# Termocouplers.net
KiCad netlist of a schematic drawn in Altium Designer
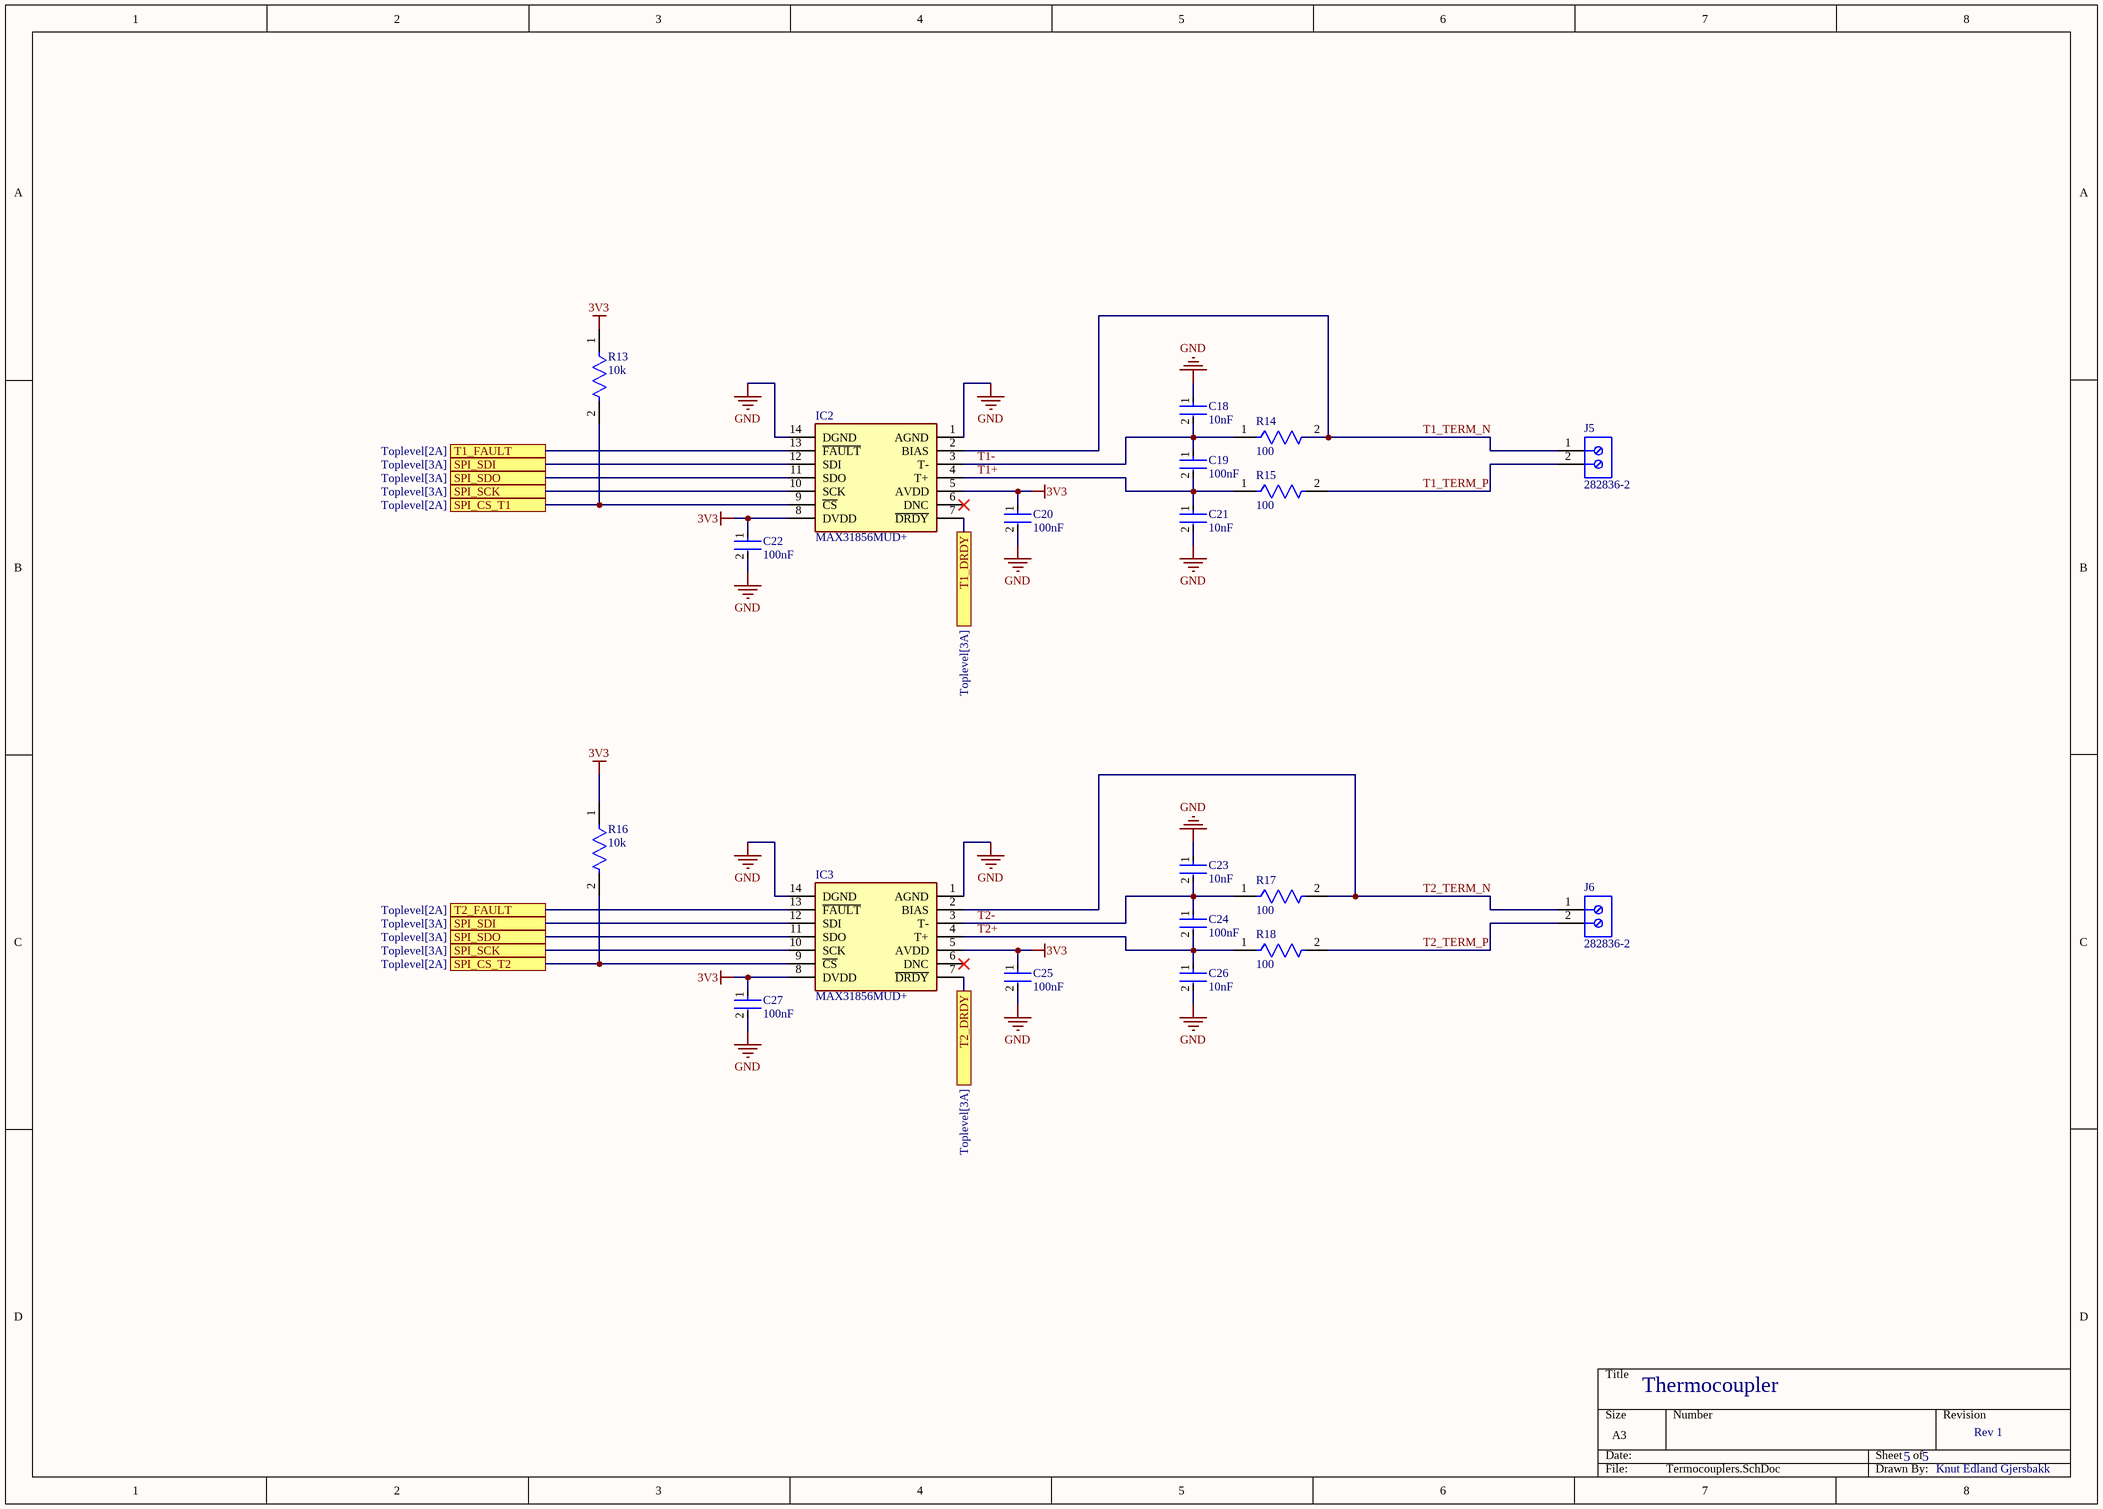
[diagram p0: Termocouplers.SchDoc]

(export (version "E")
  (design (tool "Eeschema 10.0.6"))
  (components
    (comp (ref "C18")
      (value "10nF")
      (footprint "FP-GCM188-0_1-MFG")
      (description "Ceramic Capacitor for Automotive 10nF  ±10% 100VDC X7R 0603 Paper T/R")
      (fields (field (name "VOLTAGE") "100V") (field (name "TOLERANCE") "10%"))
      (libsource (lib "Altium Content Vault") (part "02cd4be3c70576c341d710602a673aa"))
    )
    (comp (ref "C19")
      (value "100nF")
      (footprint "FP-GCM188-0_1-IPC_B")
      (description "Ceramic Capacitor for Automotive 100nF  ±10% 50VDC X8L 0603 Paper T/R")
      (fields (field (name "TOLERANCE") "10%") (field (name "VOLTAGE") "50V"))
      (libsource (lib "Altium Content Vault") (part "02cd4be3c70576c341d710602a673aa"))
    )
    (comp (ref "C20")
      (value "100nF")
      (footprint "FP-GCM188-0_1-IPC_B")
      (description "Ceramic Capacitor for Automotive 100nF  ±10% 50VDC X8L 0603 Paper T/R")
      (fields (field (name "TOLERANCE") "10%") (field (name "VOLTAGE") "50V"))
      (libsource (lib "Altium Content Vault") (part "02cd4be3c70576c341d710602a673aa"))
    )
    (comp (ref "C21")
      (value "10nF")
      (footprint "FP-GCM188-0_1-MFG")
      (description "Ceramic Capacitor for Automotive 10nF  ±10% 100VDC X7R 0603 Paper T/R")
      (fields (field (name "VOLTAGE") "100V") (field (name "TOLERANCE") "10%"))
      (libsource (lib "Altium Content Vault") (part "02cd4be3c70576c341d710602a673aa"))
    )
    (comp (ref "C22")
      (value "100nF")
      (footprint "FP-GCM188-0_1-IPC_B")
      (description "Ceramic Capacitor for Automotive 100nF  ±10% 50VDC X8L 0603 Paper T/R")
      (fields (field (name "TOLERANCE") "10%") (field (name "VOLTAGE") "50V"))
      (libsource (lib "Altium Content Vault") (part "02cd4be3c70576c341d710602a673aa"))
    )
    (comp (ref "C23")
      (value "10nF")
      (footprint "FP-GCM188-0_1-MFG")
      (description "Ceramic Capacitor for Automotive 10nF  ±10% 100VDC X7R 0603 Paper T/R")
      (fields (field (name "VOLTAGE") "100V") (field (name "TOLERANCE") "10%"))
      (libsource (lib "Altium Content Vault") (part "02cd4be3c70576c341d710602a673aa"))
    )
    (comp (ref "C24")
      (value "100nF")
      (footprint "FP-GCM188-0_1-IPC_B")
      (description "Ceramic Capacitor for Automotive 100nF  ±10% 50VDC X8L 0603 Paper T/R")
      (fields (field (name "TOLERANCE") "10%") (field (name "VOLTAGE") "50V"))
      (libsource (lib "Altium Content Vault") (part "02cd4be3c70576c341d710602a673aa"))
    )
    (comp (ref "C25")
      (value "100nF")
      (footprint "FP-GCM188-0_1-IPC_B")
      (description "Ceramic Capacitor for Automotive 100nF  ±10% 50VDC X8L 0603 Paper T/R")
      (fields (field (name "TOLERANCE") "10%") (field (name "VOLTAGE") "50V"))
      (libsource (lib "Altium Content Vault") (part "02cd4be3c70576c341d710602a673aa"))
    )
    (comp (ref "C26")
      (value "10nF")
      (footprint "FP-GCM188-0_1-MFG")
      (description "Ceramic Capacitor for Automotive 10nF  ±10% 100VDC X7R 0603 Paper T/R")
      (fields (field (name "VOLTAGE") "100V") (field (name "TOLERANCE") "10%"))
      (libsource (lib "Altium Content Vault") (part "02cd4be3c70576c341d710602a673aa"))
    )
    (comp (ref "C27")
      (value "100nF")
      (footprint "FP-GCM188-0_1-IPC_B")
      (description "Ceramic Capacitor for Automotive 100nF  ±10% 50VDC X8L 0603 Paper T/R")
      (fields (field (name "TOLERANCE") "10%") (field (name "VOLTAGE") "50V"))
      (libsource (lib "Altium Content Vault") (part "02cd4be3c70576c341d710602a673aa"))
    )
    (comp (ref "IC2")
      (value "MAX31856MUD+")
      (footprint "SamacSys:SOP65P640X110-14N")
      (description "Integrated Circuit")
      (fields (field (name "MOUSER PART NUMBER") "700-MAX31856MUD+"))
      (libsource (lib "*") (part "MAX31856MUD+"))
    )
    (comp (ref "IC3")
      (value "MAX31856MUD+")
      (footprint "SamacSys:SOP65P640X110-14N")
      (description "Integrated Circuit")
      (fields (field (name "MOUSER PART NUMBER") "700-MAX31856MUD+"))
      (libsource (lib "*") (part "MAX31856MUD+"))
    )
    (comp (ref "J5")
      (value "282836-2")
      (footprint "TECO-282836-2_V")
      (description "Female Header, Pitch 5 mm, 1 x 2 Position, Height 10 mm, Tail Length 3.5 mm, Rohs, Bulk")
      (fields (field (name "VOLTAGE") "300V") (field (name "MANUFACTURER") "TE Connectivity"))
      (libsource (lib "Altium Content Vault") (part "CN-1P-F-TB2"))
    )
    (comp (ref "J6")
      (value "282836-2")
      (footprint "TECO-282836-2_V")
      (description "Female Header, Pitch 5 mm, 1 x 2 Position, Height 10 mm, Tail Length 3.5 mm, Rohs, Bulk")
      (fields (field (name "VOLTAGE") "300V") (field (name "MANUFACTURER") "TE Connectivity"))
      (libsource (lib "Altium Content Vault") (part "CN-1P-F-TB2"))
    )
    (comp (ref "R13")
      (value "10k")
      (footprint "FP-RT0603-IPC_C")
      (description "RES SMD 10K OHM 1% 1/10W 0603\r\nRT0603FRE0710KL")
      (fields
        (field (name "MANUFACTURER") "Yageo")
        (field (name "OCTOPART") "https://octopart.com/rt0603fre0710kl-yageo-40009243")
      )
      (libsource (lib "Altium Content Vault") (part "1029c3af85768c4190bb7ad29bc67b5"))
    )
    (comp (ref "R14")
      (value "100")
      (footprint "FP-CR0603-IPC_A")
      (description "AEC-Q200 Compliant Chip Resistors 0603 100Ω 0.1W 1% 100ppm/°C")
      (libsource (lib "Altium Content Vault") (part "1029c3af85768c4190bb7ad29bc67b5"))
    )
    (comp (ref "R15")
      (value "100")
      (footprint "FP-CR0603-IPC_A")
      (description "AEC-Q200 Compliant Chip Resistors 0603 100Ω 0.1W 1% 100ppm/°C")
      (libsource (lib "Altium Content Vault") (part "1029c3af85768c4190bb7ad29bc67b5"))
    )
    (comp (ref "R16")
      (value "10k")
      (footprint "FP-RT0603-IPC_C")
      (description "RES SMD 10K OHM 1% 1/10W 0603\r\nRT0603FRE0710KL")
      (fields
        (field (name "MANUFACTURER") "Yageo")
        (field (name "OCTOPART") "https://octopart.com/rt0603fre0710kl-yageo-40009243")
      )
      (libsource (lib "Altium Content Vault") (part "1029c3af85768c4190bb7ad29bc67b5"))
    )
    (comp (ref "R17")
      (value "100")
      (footprint "FP-CR0603-IPC_A")
      (description "AEC-Q200 Compliant Chip Resistors 0603 100Ω 0.1W 1% 100ppm/°C")
      (libsource (lib "Altium Content Vault") (part "1029c3af85768c4190bb7ad29bc67b5"))
    )
    (comp (ref "R18")
      (value "100")
      (footprint "FP-CR0603-IPC_A")
      (description "AEC-Q200 Compliant Chip Resistors 0603 100Ω 0.1W 1% 100ppm/°C")
      (libsource (lib "Altium Content Vault") (part "1029c3af85768c4190bb7ad29bc67b5"))
    )
  )
  (nets
    (net (code "1") (name "/SPI_CS_T1") (class "Default")
      (node (ref "IC2") (pin "9") (pinfunction "~{CS}_9") (pintype "passive"))
      (node (ref "R13") (pin "2") (pinfunction "2_2") (pintype "passive"))
    )
    (net (code "2") (name "/SPI_CS_T2") (class "Default")
      (node (ref "IC3") (pin "9") (pinfunction "~{CS}_9") (pintype "passive"))
      (node (ref "R16") (pin "2") (pinfunction "2_2") (pintype "passive"))
    )
    (net (code "3") (name "/SPI_SCK") (class "Default")
      (node (ref "IC2") (pin "10") (pinfunction "SCK_10") (pintype "passive"))
      (node (ref "IC3") (pin "10") (pinfunction "SCK_10") (pintype "passive"))
    )
    (net (code "4") (name "/SPI_SDI") (class "Default")
      (node (ref "IC2") (pin "12") (pinfunction "SDI_12") (pintype "passive"))
      (node (ref "IC3") (pin "12") (pinfunction "SDI_12") (pintype "passive"))
    )
    (net (code "5") (name "/SPI_SDO") (class "Default")
      (node (ref "IC2") (pin "11") (pinfunction "SDO_11") (pintype "passive"))
      (node (ref "IC3") (pin "11") (pinfunction "SDO_11") (pintype "passive"))
    )
    (net (code "6") (name "/T1+") (class "Default")
      (node (ref "C19") (pin "2") (pinfunction "2_2") (pintype "passive"))
      (node (ref "C21") (pin "1") (pinfunction "1_1") (pintype "passive"))
      (node (ref "IC2") (pin "4") (pinfunction "T+_4") (pintype "passive"))
      (node (ref "R15") (pin "1") (pinfunction "1_1") (pintype "passive"))
    )
    (net (code "7") (name "/T1-") (class "Default")
      (node (ref "C18") (pin "2") (pinfunction "2_2") (pintype "passive"))
      (node (ref "C19") (pin "1") (pinfunction "1_1") (pintype "passive"))
      (node (ref "IC2") (pin "3") (pinfunction "T-_3") (pintype "passive"))
      (node (ref "R14") (pin "1") (pinfunction "1_1") (pintype "passive"))
    )
    (net (code "8") (name "/T1_DRDY") (class "Default")
      (node (ref "IC2") (pin "7") (pinfunction "~{DRDY}_7") (pintype "passive"))
    )
    (net (code "9") (name "/T1_FAULT") (class "Default")
      (node (ref "IC2") (pin "13") (pinfunction "~{FAULT}_13") (pintype "passive"))
    )
    (net (code "10") (name "/T1_TERM_N") (class "Default")
      (node (ref "IC2") (pin "2") (pinfunction "BIAS_2") (pintype "passive"))
      (node (ref "J5") (pin "1") (pinfunction "1_1") (pintype "passive"))
      (node (ref "R14") (pin "2") (pinfunction "2_2") (pintype "passive"))
    )
    (net (code "11") (name "/T1_TERM_P") (class "Default")
      (node (ref "J5") (pin "2") (pinfunction "2_2") (pintype "passive"))
      (node (ref "R15") (pin "2") (pinfunction "2_2") (pintype "passive"))
    )
    (net (code "12") (name "/T2+") (class "Default")
      (node (ref "C24") (pin "2") (pinfunction "2_2") (pintype "passive"))
      (node (ref "C26") (pin "1") (pinfunction "1_1") (pintype "passive"))
      (node (ref "IC3") (pin "4") (pinfunction "T+_4") (pintype "passive"))
      (node (ref "R18") (pin "1") (pinfunction "1_1") (pintype "passive"))
    )
    (net (code "13") (name "/T2-") (class "Default")
      (node (ref "C23") (pin "2") (pinfunction "2_2") (pintype "passive"))
      (node (ref "C24") (pin "1") (pinfunction "1_1") (pintype "passive"))
      (node (ref "IC3") (pin "3") (pinfunction "T-_3") (pintype "passive"))
      (node (ref "R17") (pin "1") (pinfunction "1_1") (pintype "passive"))
    )
    (net (code "14") (name "/T2_DRDY") (class "Default")
      (node (ref "IC3") (pin "7") (pinfunction "~{DRDY}_7") (pintype "passive"))
    )
    (net (code "15") (name "/T2_FAULT") (class "Default")
      (node (ref "IC3") (pin "13") (pinfunction "~{FAULT}_13") (pintype "passive"))
    )
    (net (code "16") (name "/T2_TERM_N") (class "Default")
      (node (ref "IC3") (pin "2") (pinfunction "BIAS_2") (pintype "passive"))
      (node (ref "J6") (pin "1") (pinfunction "1_1") (pintype "passive"))
      (node (ref "R17") (pin "2") (pinfunction "2_2") (pintype "passive"))
    )
    (net (code "17") (name "/T2_TERM_P") (class "Default")
      (node (ref "J6") (pin "2") (pinfunction "2_2") (pintype "passive"))
      (node (ref "R18") (pin "2") (pinfunction "2_2") (pintype "passive"))
    )
    (net (code "18") (name "3V3") (class "Default")
      (node (ref "C20") (pin "1") (pinfunction "1_1") (pintype "passive"))
      (node (ref "C22") (pin "1") (pinfunction "1_1") (pintype "passive"))
      (node (ref "C25") (pin "1") (pinfunction "1_1") (pintype "passive"))
      (node (ref "C27") (pin "1") (pinfunction "1_1") (pintype "passive"))
      (node (ref "IC2") (pin "5") (pinfunction "AVDD_5") (pintype "passive"))
      (node (ref "IC2") (pin "8") (pinfunction "DVDD_8") (pintype "passive"))
      (node (ref "IC3") (pin "5") (pinfunction "AVDD_5") (pintype "passive"))
      (node (ref "IC3") (pin "8") (pinfunction "DVDD_8") (pintype "passive"))
      (node (ref "R13") (pin "1") (pinfunction "1_1") (pintype "passive"))
      (node (ref "R16") (pin "1") (pinfunction "1_1") (pintype "passive"))
    )
    (net (code "19") (name "GND") (class "Default")
      (node (ref "C18") (pin "1") (pinfunction "1_1") (pintype "passive"))
      (node (ref "C20") (pin "2") (pinfunction "2_2") (pintype "passive"))
      (node (ref "C21") (pin "2") (pinfunction "2_2") (pintype "passive"))
      (node (ref "C22") (pin "2") (pinfunction "2_2") (pintype "passive"))
      (node (ref "C23") (pin "1") (pinfunction "1_1") (pintype "passive"))
      (node (ref "C25") (pin "2") (pinfunction "2_2") (pintype "passive"))
      (node (ref "C26") (pin "2") (pinfunction "2_2") (pintype "passive"))
      (node (ref "C27") (pin "2") (pinfunction "2_2") (pintype "passive"))
      (node (ref "IC2") (pin "1") (pinfunction "AGND_1") (pintype "passive"))
      (node (ref "IC2") (pin "14") (pinfunction "DGND_14") (pintype "passive"))
      (node (ref "IC3") (pin "1") (pinfunction "AGND_1") (pintype "passive"))
      (node (ref "IC3") (pin "14") (pinfunction "DGND_14") (pintype "passive"))
    )
    (net (code "20") (name "unconnected-(IC2-DNC-Pad6)") (class "Default")
      (node (ref "IC2") (pin "6") (pinfunction "DNC_6") (pintype "passive+no_connect"))
    )
    (net (code "21") (name "unconnected-(IC3-DNC-Pad6)") (class "Default")
      (node (ref "IC3") (pin "6") (pinfunction "DNC_6") (pintype "passive+no_connect"))
    )
  )
)
